# Explore-Labs-3D-Accelerometer-3D-Magneto.net
KiCad netlist of a schematic drawn in EAGLE
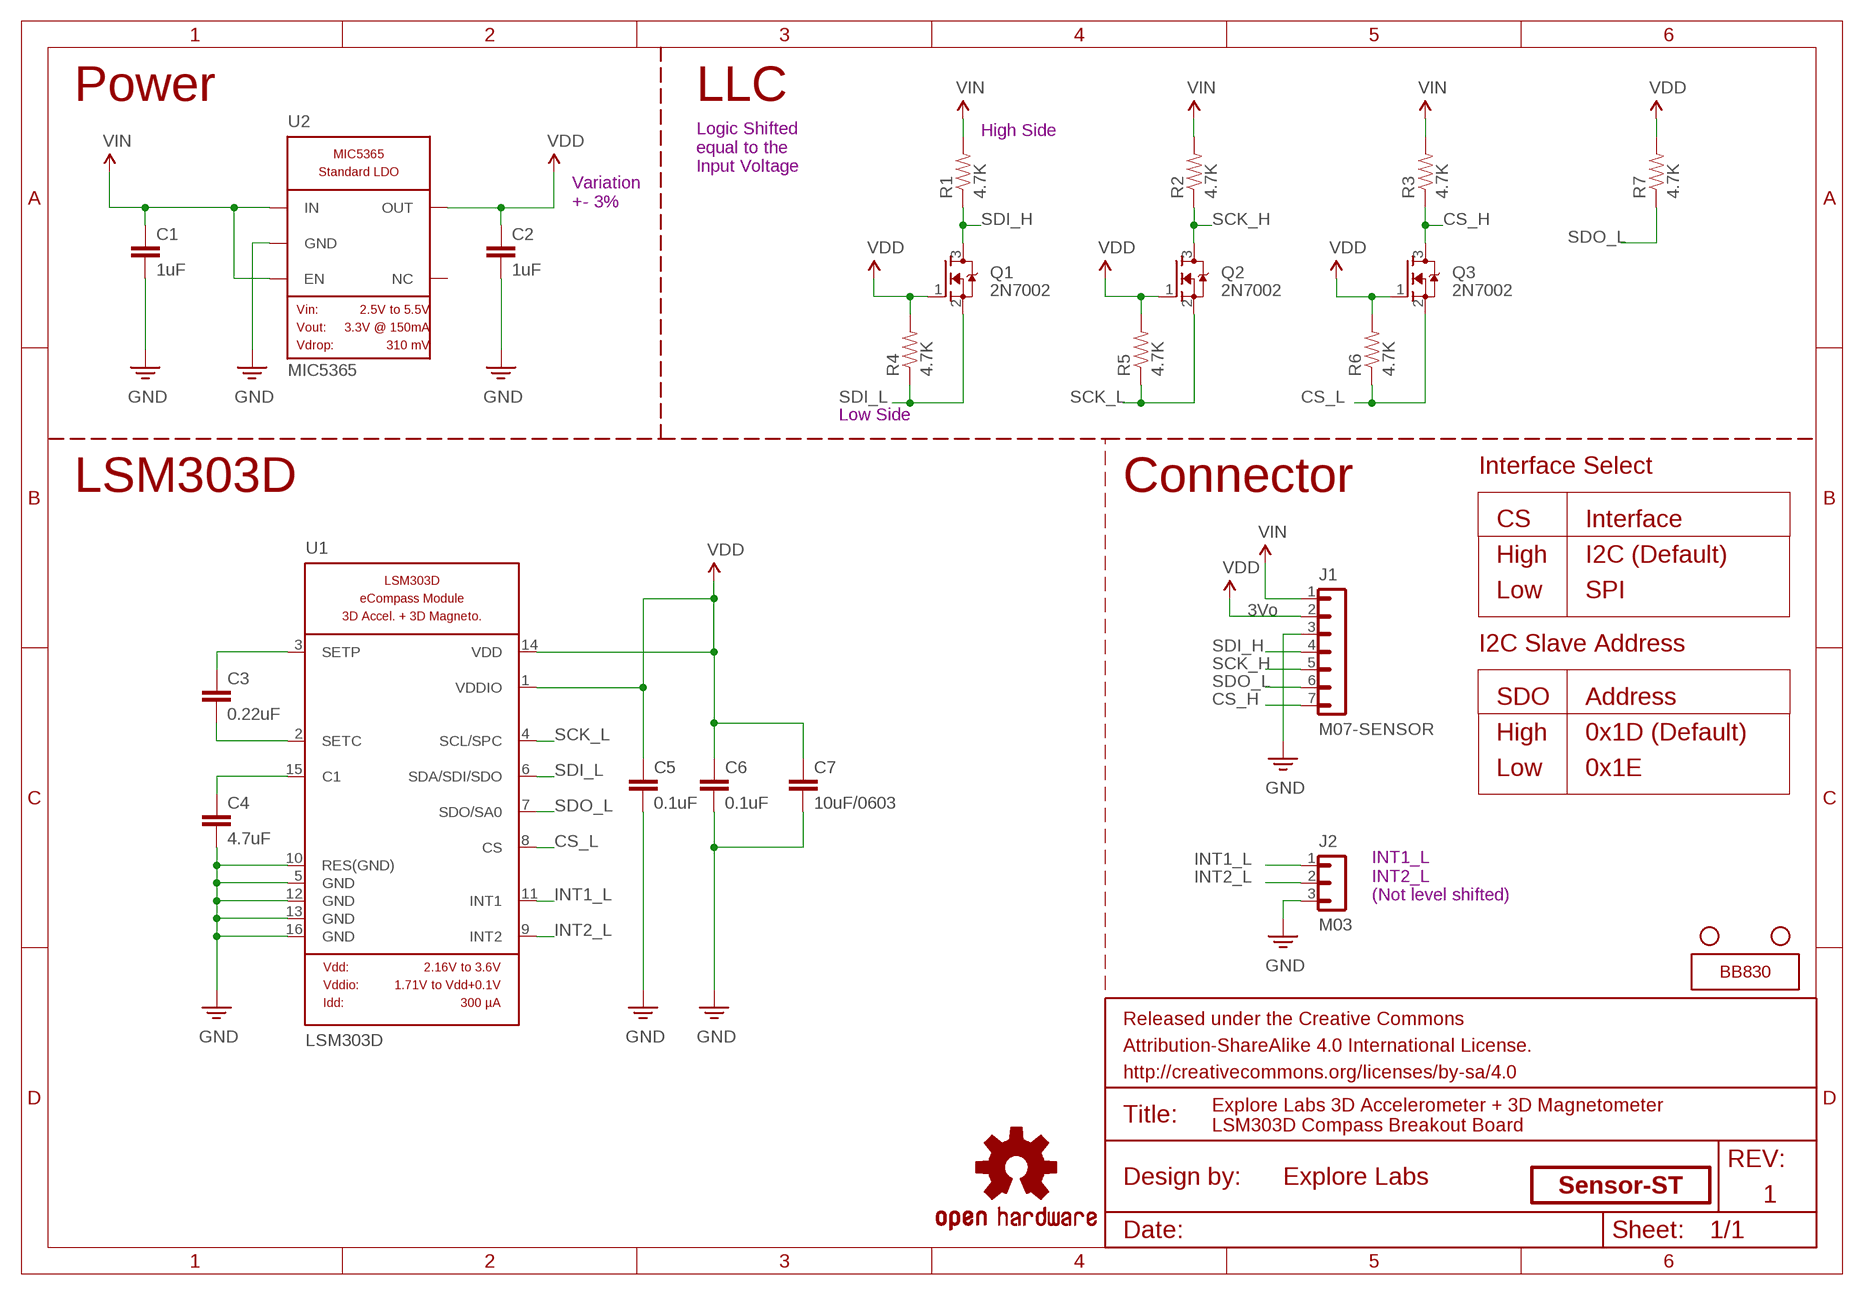
[diagram p0: schematic, sheet 1]

(export (version "E")
  (design (tool "Eeschema 10.0.6"))
  (components
    (comp (ref "C1")
      (value "1uF")
      (footprint "eagle-import:0402-CAP")
      (libsource (lib "eagle-import") (part "CAPACITOR-0402"))
    )
    (comp (ref "C2")
      (value "1uF")
      (footprint "eagle-import:0402-CAP")
      (libsource (lib "eagle-import") (part "CAPACITOR-0402"))
    )
    (comp (ref "C3")
      (value "0.22uF")
      (footprint "eagle-import:0402-CAP")
      (libsource (lib "eagle-import") (part "CAPACITOR-0402"))
    )
    (comp (ref "C4")
      (value "4.7uF")
      (footprint "eagle-import:0402-CAP")
      (libsource (lib "eagle-import") (part "CAPACITOR-0402"))
    )
    (comp (ref "C5")
      (value "0.1uF")
      (footprint "eagle-import:0402-CAP")
      (libsource (lib "eagle-import") (part "CAPACITOR-0402"))
    )
    (comp (ref "C6")
      (value "0.1uF")
      (footprint "eagle-import:0402-CAP")
      (libsource (lib "eagle-import") (part "CAPACITOR-0402"))
    )
    (comp (ref "C7")
      (value "10uF/0603")
      (footprint "eagle-import:0603-CAP")
      (libsource (lib "eagle-import") (part "CAPACITOR-0603"))
    )
    (comp (ref "H1")
      (value "STAND-OFF")
      (footprint "eagle-import:STAND-OFF")
      (libsource (lib "eagle-import") (part "STAND-OFF"))
    )
    (comp (ref "H2")
      (value "STAND-OFF")
      (footprint "eagle-import:STAND-OFF")
      (libsource (lib "eagle-import") (part "STAND-OFF"))
    )
    (comp (ref "J1")
      (value "M07-SENSOR")
      (footprint "eagle-import:1X07-SENSOR-SPI")
      (libsource (lib "eagle-import") (part "M07-SENSOR"))
    )
    (comp (ref "J2")
      (value "M03")
      (footprint "eagle-import:1X03")
      (libsource (lib "eagle-import") (part "M03"))
    )
    (comp (ref "Q1")
      (value "2N7002")
      (footprint "eagle-import:SOT23")
      (libsource (lib "eagle-import") (part "MOSFET-N-2N7002P"))
    )
    (comp (ref "Q2")
      (value "2N7002")
      (footprint "eagle-import:SOT23")
      (libsource (lib "eagle-import") (part "MOSFET-N-2N7002P"))
    )
    (comp (ref "Q3")
      (value "2N7002")
      (footprint "eagle-import:SOT23")
      (libsource (lib "eagle-import") (part "MOSFET-N-2N7002P"))
    )
    (comp (ref "R1")
      (value "4.7K")
      (footprint "eagle-import:0402-RES")
      (libsource (lib "eagle-import") (part "RESISTOR-0402"))
    )
    (comp (ref "R2")
      (value "4.7K")
      (footprint "eagle-import:0402-RES")
      (libsource (lib "eagle-import") (part "RESISTOR-0402"))
    )
    (comp (ref "R3")
      (value "4.7K")
      (footprint "eagle-import:0402-RES")
      (libsource (lib "eagle-import") (part "RESISTOR-0402"))
    )
    (comp (ref "R4")
      (value "4.7K")
      (footprint "eagle-import:0402-RES")
      (libsource (lib "eagle-import") (part "RESISTOR-0402"))
    )
    (comp (ref "R5")
      (value "4.7K")
      (footprint "eagle-import:0402-RES")
      (libsource (lib "eagle-import") (part "RESISTOR-0402"))
    )
    (comp (ref "R6")
      (value "4.7K")
      (footprint "eagle-import:0402-RES")
      (libsource (lib "eagle-import") (part "RESISTOR-0402"))
    )
    (comp (ref "R7")
      (value "4.7K")
      (footprint "eagle-import:0402-RES")
      (libsource (lib "eagle-import") (part "RESISTOR-0402"))
    )
    (comp (ref "U1")
      (value "LSM303D")
      (footprint "eagle-import:LGA16-LSM303D")
      (libsource (lib "eagle-import") (part "LSM303D"))
    )
    (comp (ref "U2")
      (value "MIC5365")
      (footprint "eagle-import:SOT23-LDO")
      (libsource (lib "eagle-import") (part "MIC5365"))
    )
    (comp (ref "ZZ1")
      (value "EXPLORE-LABS-LOGO-2-0.25")
      (footprint "eagle-import:EXLABS_LOGO_0.25")
      (libsource (lib "eagle-import") (part "EXPLORE-LABS-LOGO-2-0.25"))
    )
    (comp (ref "ZZ2")
      (value "OSHW-LOGOBOTTOM")
      (footprint "eagle-import:OSHW-LOGO-M-BOTTOM")
      (libsource (lib "eagle-import") (part "OSHW-LOGOBOTTOM"))
    )
    (comp (ref "ZZ3")
      (value "SENSOR-ST")
      (footprint "eagle-import:SENSOR-ST")
      (libsource (lib "eagle-import") (part "SENSOR-ST"))
    )
    (comp (ref "ZZ4")
      (value "BREADBOARD-830")
      (footprint "eagle-import:BREADBOARD-830")
      (libsource (lib "eagle-import") (part "BREADBOARD-830"))
    )
  )
  (nets
    (net (code "1") (name "/CS_H") (class "Default")
      (node (ref "J1") (pin "7") (pinfunction "7_7") (pintype "passive"))
      (node (ref "Q3") (pin "3") (pinfunction "D_3") (pintype "bidirectional"))
      (node (ref "R3") (pin "1") (pinfunction "1_1") (pintype "passive"))
    )
    (net (code "2") (name "/CS_L") (class "Default")
      (node (ref "Q3") (pin "2") (pinfunction "S_2") (pintype "bidirectional"))
      (node (ref "R6") (pin "1") (pinfunction "1_1") (pintype "passive"))
      (node (ref "U1") (pin "8") (pinfunction "CS_8") (pintype "bidirectional"))
    )
    (net (code "3") (name "/INT1_L") (class "Default")
      (node (ref "J2") (pin "1") (pinfunction "1_1") (pintype "passive"))
      (node (ref "U1") (pin "11") (pinfunction "INT1_11") (pintype "bidirectional"))
    )
    (net (code "4") (name "/INT2_L") (class "Default")
      (node (ref "J2") (pin "2") (pinfunction "2_2") (pintype "passive"))
      (node (ref "U1") (pin "9") (pinfunction "INT2_9") (pintype "bidirectional"))
    )
    (net (code "5") (name "/SCK_H") (class "Default")
      (node (ref "J1") (pin "5") (pinfunction "5_5") (pintype "passive"))
      (node (ref "Q2") (pin "3") (pinfunction "D_3") (pintype "bidirectional"))
      (node (ref "R2") (pin "1") (pinfunction "1_1") (pintype "passive"))
    )
    (net (code "6") (name "/SCK_L") (class "Default")
      (node (ref "Q2") (pin "2") (pinfunction "S_2") (pintype "bidirectional"))
      (node (ref "R5") (pin "1") (pinfunction "1_1") (pintype "passive"))
      (node (ref "U1") (pin "4") (pinfunction "SCL/SPC_4") (pintype "bidirectional"))
    )
    (net (code "7") (name "/SDI_H") (class "Default")
      (node (ref "J1") (pin "4") (pinfunction "4_4") (pintype "passive"))
      (node (ref "Q1") (pin "3") (pinfunction "D_3") (pintype "bidirectional"))
      (node (ref "R1") (pin "1") (pinfunction "1_1") (pintype "passive"))
    )
    (net (code "8") (name "/SDI_L") (class "Default")
      (node (ref "Q1") (pin "2") (pinfunction "S_2") (pintype "bidirectional"))
      (node (ref "R4") (pin "1") (pinfunction "1_1") (pintype "passive"))
      (node (ref "U1") (pin "6") (pinfunction "SDA/SDI/SDO_6") (pintype "bidirectional"))
    )
    (net (code "9") (name "/SDO_L") (class "Default")
      (node (ref "J1") (pin "6") (pinfunction "6_6") (pintype "passive"))
      (node (ref "R7") (pin "1") (pinfunction "1_1") (pintype "passive"))
      (node (ref "U1") (pin "7") (pinfunction "SDO/SA0_7") (pintype "bidirectional"))
    )
    (net (code "10") (name "GND") (class "Default")
      (node (ref "C1") (pin "2") (pinfunction "2_2") (pintype "passive"))
      (node (ref "C2") (pin "2") (pinfunction "2_2") (pintype "passive"))
      (node (ref "C4") (pin "2") (pinfunction "2_2") (pintype "passive"))
      (node (ref "C5") (pin "2") (pinfunction "2_2") (pintype "passive"))
      (node (ref "C6") (pin "2") (pinfunction "2_2") (pintype "passive"))
      (node (ref "C7") (pin "2") (pinfunction "2_2") (pintype "passive"))
      (node (ref "J1") (pin "3") (pinfunction "3_3") (pintype "passive"))
      (node (ref "J2") (pin "3") (pinfunction "3_3") (pintype "passive"))
      (node (ref "U1") (pin "10") (pinfunction "RES(GND)_10") (pintype "power_in"))
      (node (ref "U1") (pin "12") (pinfunction "GND_12") (pintype "power_in"))
      (node (ref "U1") (pin "13") (pinfunction "GND_13") (pintype "power_in"))
      (node (ref "U1") (pin "16") (pinfunction "GND_16") (pintype "power_in"))
      (node (ref "U1") (pin "5") (pinfunction "GND_5") (pintype "power_in"))
      (node (ref "U2") (pin "2") (pinfunction "GND_2") (pintype "power_in"))
    )
    (net (code "11") (name "Net-(U1-C1)") (class "Default")
      (node (ref "C4") (pin "1") (pinfunction "1_1") (pintype "passive"))
      (node (ref "U1") (pin "15") (pinfunction "C1_15") (pintype "bidirectional"))
    )
    (net (code "12") (name "Net-(U1-SETC)") (class "Default")
      (node (ref "C3") (pin "2") (pinfunction "2_2") (pintype "passive"))
      (node (ref "U1") (pin "2") (pinfunction "SETC_2") (pintype "bidirectional"))
    )
    (net (code "13") (name "Net-(U1-SETP)") (class "Default")
      (node (ref "C3") (pin "1") (pinfunction "1_1") (pintype "passive"))
      (node (ref "U1") (pin "3") (pinfunction "SETP_3") (pintype "bidirectional"))
    )
    (net (code "14") (name "VDD") (class "Default")
      (node (ref "C2") (pin "1") (pinfunction "1_1") (pintype "passive"))
      (node (ref "C5") (pin "1") (pinfunction "1_1") (pintype "passive"))
      (node (ref "C6") (pin "1") (pinfunction "1_1") (pintype "passive"))
      (node (ref "C7") (pin "1") (pinfunction "1_1") (pintype "passive"))
      (node (ref "J1") (pin "2") (pinfunction "2_2") (pintype "passive"))
      (node (ref "Q1") (pin "1") (pinfunction "G_1") (pintype "bidirectional"))
      (node (ref "Q2") (pin "1") (pinfunction "G_1") (pintype "bidirectional"))
      (node (ref "Q3") (pin "1") (pinfunction "G_1") (pintype "bidirectional"))
      (node (ref "R4") (pin "2") (pinfunction "2_2") (pintype "passive"))
      (node (ref "R5") (pin "2") (pinfunction "2_2") (pintype "passive"))
      (node (ref "R6") (pin "2") (pinfunction "2_2") (pintype "passive"))
      (node (ref "R7") (pin "2") (pinfunction "2_2") (pintype "passive"))
      (node (ref "U1") (pin "1") (pinfunction "VDDIO_1") (pintype "power_in"))
      (node (ref "U1") (pin "14") (pinfunction "VDD_14") (pintype "power_in"))
      (node (ref "U2") (pin "5") (pinfunction "OUT_5") (pintype "power_in"))
    )
    (net (code "15") (name "VIN") (class "Default")
      (node (ref "C1") (pin "1") (pinfunction "1_1") (pintype "passive"))
      (node (ref "J1") (pin "1") (pinfunction "1_1") (pintype "passive"))
      (node (ref "R1") (pin "2") (pinfunction "2_2") (pintype "passive"))
      (node (ref "R2") (pin "2") (pinfunction "2_2") (pintype "passive"))
      (node (ref "R3") (pin "2") (pinfunction "2_2") (pintype "passive"))
      (node (ref "U2") (pin "1") (pinfunction "IN_1") (pintype "power_in"))
      (node (ref "U2") (pin "3") (pinfunction "EN_3") (pintype "input"))
    )
    (net (code "16") (name "unconnected-(U2-NC-Pad4)") (class "Default")
      (node (ref "U2") (pin "4") (pinfunction "NC_4") (pintype "no_connect"))
    )
  )
)
